# LVDS_IFC.net
KiCad netlist of a schematic drawn in Altium Designer
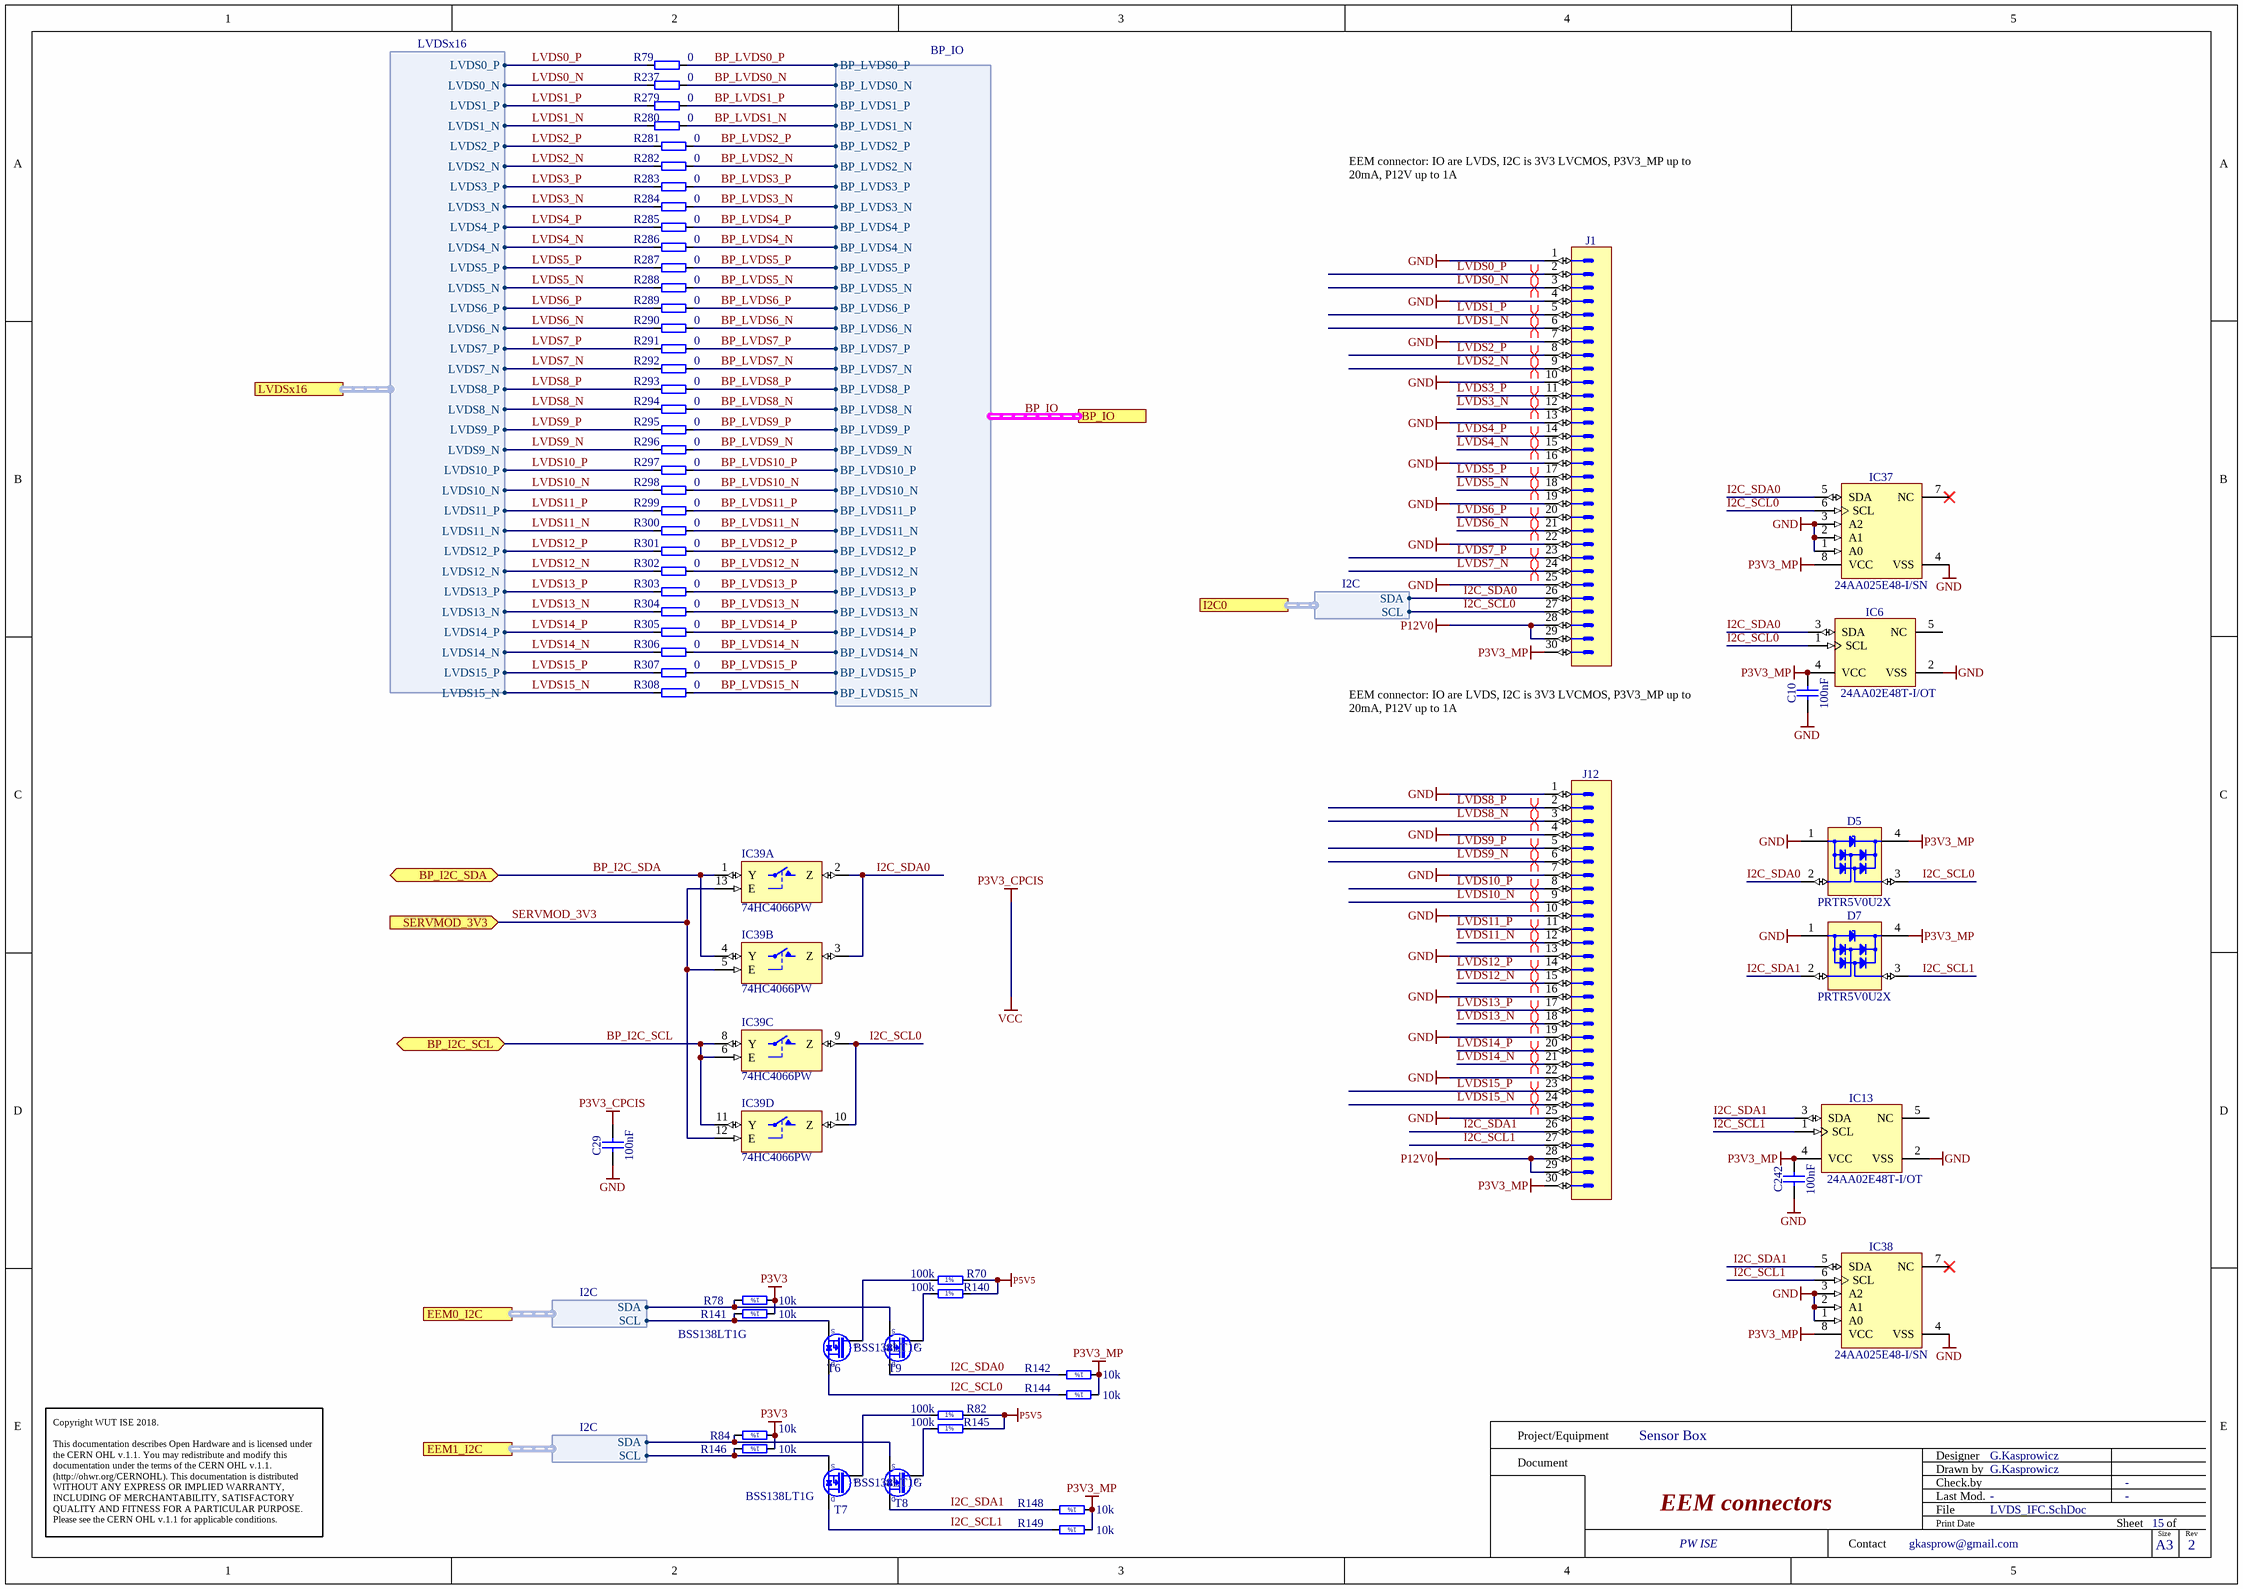
[diagram p0: LVDS_IFC.SchDoc]

(export (version "E")
  (design (tool "Eeschema 10.0.6"))
  (components
    (comp (ref "C10")
      (value "100nF")
      (footprint "CAPC1005X55N")
      (description "Non-polarised capacitor")
      (fields
        (field (name "PART NUMBER") "CC0402_100NF_16V_10%_X5R")
        (field (name "VOLTAGE") "16V")
        (field (name "AUTHOR") "CERN DEM JLC")
      )
      (libsource (lib "Capacitors") (part "Capacitor - non polarized"))
    )
    (comp (ref "C29")
      (value "100nF")
      (footprint "CAPC1005X55N")
      (description "Non-polarised capacitor")
      (fields
        (field (name "PART NUMBER") "CC0402_100NF_16V_10%_X5R")
        (field (name "VOLTAGE") "16V")
        (field (name "AUTHOR") "CERN DEM JLC")
      )
      (libsource (lib "Capacitors") (part "Capacitor - non polarized"))
    )
    (comp (ref "C242")
      (value "100nF")
      (footprint "CAPC1005X55N")
      (description "Non-polarised capacitor")
      (fields
        (field (name "PART NUMBER") "CC0402_100NF_16V_10%_X5R")
        (field (name "VOLTAGE") "16V")
        (field (name "AUTHOR") "CERN DEM JLC")
      )
      (libsource (lib "Capacitors") (part "Capacitor - non polarized"))
    )
    (comp (ref "D5")
      (value "PRTR5V0U2X")
      (footprint "SOT190P230X110-4N")
      (description "Ultra Low Capacitance Double Rail-to-Rail ESD Protection Diode")
      (fields
        (field (name "VOLTAGE") "5.5V")
        (field (name "MANUFACTURER") "NXP SEMICONDUCTORS")
        (field (name "AUTHOR") "CERN DEM JLC")
      )
      (libsource (lib "ICs And Semiconductors") (part "PRTR5V0U2X"))
    )
    (comp (ref "D7")
      (value "PRTR5V0U2X")
      (footprint "SOT190P230X110-4N")
      (description "Ultra Low Capacitance Double Rail-to-Rail ESD Protection Diode")
      (fields
        (field (name "VOLTAGE") "5.5V")
        (field (name "MANUFACTURER") "NXP SEMICONDUCTORS")
        (field (name "AUTHOR") "CERN DEM JLC")
      )
      (libsource (lib "ICs And Semiconductors") (part "PRTR5V0U2X"))
    )
    (comp (ref "IC6")
      (value "24AA02E48T-I/OT")
      (footprint "SOT95P280X145-5N")
      (description "1.7V-5.5V, 2K I2C Serial EEPROM With EUI-48 Node Identity")
      (fields (field (name "MANUFACTURER") "MICROCHIP TECHNOLOGY") (field (name "AUTHOR") "CERN DEM MR"))
      (libsource (lib "ICs And Semiconductors") (part "24AA02E48T-I/OT"))
    )
    (comp (ref "IC13")
      (value "24AA02E48T-I/OT")
      (footprint "SOT95P280X145-5N")
      (description "1.7V-5.5V, 2K I2C Serial EEPROM With EUI-48 Node Identity")
      (fields (field (name "MANUFACTURER") "MICROCHIP TECHNOLOGY") (field (name "AUTHOR") "CERN DEM MR"))
      (libsource (lib "ICs And Semiconductors") (part "24AA02E48T-I/OT"))
    )
    (comp (ref "IC37")
      (value "24AA025E48-I/SN")
      (footprint "SOIC127P600X175-8N")
      (description "1.7V-5.5V, 2K I2C™ Serial EEPROMs with EUI-48™ Node Identity")
      (fields (field (name "MANUFACTURER") "MICROCHIP TECHNOLOGY") (field (name "AUTHOR") "CERN DEM MR"))
      (libsource (lib "ICs And Semiconductors") (part "24AA025E48-I/SN"))
    )
    (comp (ref "IC38")
      (value "24AA025E48-I/SN")
      (footprint "SOIC127P600X175-8N")
      (description "1.7V-5.5V, 2K I2C™ Serial EEPROMs with EUI-48™ Node Identity")
      (fields (field (name "MANUFACTURER") "MICROCHIP TECHNOLOGY") (field (name "AUTHOR") "CERN DEM MR"))
      (libsource (lib "ICs And Semiconductors") (part "24AA025E48-I/SN"))
    )
    (comp (ref "IC39")
      (value "74HC4066PW")
      (footprint "SOP65P640X110-14N")
      (fields (field (name "MANUFACTURER") "NXP SEMICONDUCTORS") (field (name "AUTHOR") "CERN DEM JLC"))
      (libsource (lib "ICs And Semiconductors") (part "4066"))
    )
    (comp (ref "J1")
      (value "~")
      (footprint "3M_N2530-6002RB")
      (description "Connector 30 Male")
      (fields
        (field (name "PART NUMBER") "3M_N2530-6002RB")
        (field (name "MANUFACTURER") "3M")
        (field (name "AUTHOR") "CERN DEM JLC")
      )
      (libsource (lib "Connectors") (part "Connector 30 Male"))
    )
    (comp (ref "J12")
      (value "~")
      (footprint "3M_N2530-6002RB")
      (description "Connector 30 Male")
      (fields
        (field (name "PART NUMBER") "3M_N2530-6002RB")
        (field (name "MANUFACTURER") "3M")
        (field (name "AUTHOR") "CERN DEM JLC")
      )
      (libsource (lib "Connectors") (part "Connector 30 Male"))
    )
    (comp (ref "R70")
      (value "100k")
      (footprint "RESC1005X40N")
      (description "Resistor - 1%")
      (fields
        (field (name "PART NUMBER") "R0402_100K_1%_0.0625W_100PPM")
        (field (name "POWER") "0.0625W")
        (field (name "AUTHOR") "CERN DEM JLC")
      )
      (libsource (lib "Resistors") (part "Resistor - 1%"))
    )
    (comp (ref "R78")
      (value "10k")
      (footprint "RESC1005X40N")
      (description "Resistor - 1%")
      (fields
        (field (name "PART NUMBER") "R0402_10K_1%_0.0625W_100PPM")
        (field (name "POWER") "0.0625W")
        (field (name "AUTHOR") "CERN DEM JLC")
      )
      (libsource (lib "Resistors") (part "Resistor - 1%"))
    )
    (comp (ref "R79")
      (value "0")
      (footprint "RESC1005X35N")
      (description "Resistor")
      (fields
        (field (name "PART NUMBER") "R0402_0R_JUMPER")
        (field (name "MANUFACTURER") "GENERIC")
        (field (name "AUTHOR") "CERN DEM JLC")
      )
      (libsource (lib "Resistors") (part "Resistor"))
    )
    (comp (ref "R82")
      (value "100k")
      (footprint "RESC1005X40N")
      (description "Resistor - 1%")
      (fields
        (field (name "PART NUMBER") "R0402_100K_1%_0.0625W_100PPM")
        (field (name "POWER") "0.0625W")
        (field (name "AUTHOR") "CERN DEM JLC")
      )
      (libsource (lib "Resistors") (part "Resistor - 1%"))
    )
    (comp (ref "R84")
      (value "10k")
      (footprint "RESC1005X40N")
      (description "Resistor - 1%")
      (fields
        (field (name "PART NUMBER") "R0402_10K_1%_0.0625W_100PPM")
        (field (name "POWER") "0.0625W")
        (field (name "AUTHOR") "CERN DEM JLC")
      )
      (libsource (lib "Resistors") (part "Resistor - 1%"))
    )
    (comp (ref "R140")
      (value "100k")
      (footprint "RESC1005X40N")
      (description "Resistor - 1%")
      (fields
        (field (name "PART NUMBER") "R0402_100K_1%_0.0625W_100PPM")
        (field (name "POWER") "0.0625W")
        (field (name "AUTHOR") "CERN DEM JLC")
      )
      (libsource (lib "Resistors") (part "Resistor - 1%"))
    )
    (comp (ref "R141")
      (value "10k")
      (footprint "RESC1005X40N")
      (description "Resistor - 1%")
      (fields
        (field (name "PART NUMBER") "R0402_10K_1%_0.0625W_100PPM")
        (field (name "POWER") "0.0625W")
        (field (name "AUTHOR") "CERN DEM JLC")
      )
      (libsource (lib "Resistors") (part "Resistor - 1%"))
    )
    (comp (ref "R142")
      (value "10k")
      (footprint "RESC1005X40N")
      (description "Resistor - 1%")
      (fields
        (field (name "PART NUMBER") "R0402_10K_1%_0.0625W_100PPM")
        (field (name "POWER") "0.0625W")
        (field (name "AUTHOR") "CERN DEM JLC")
      )
      (libsource (lib "Resistors") (part "Resistor - 1%"))
    )
    (comp (ref "R144")
      (value "10k")
      (footprint "RESC1005X40N")
      (description "Resistor - 1%")
      (fields
        (field (name "PART NUMBER") "R0402_10K_1%_0.0625W_100PPM")
        (field (name "POWER") "0.0625W")
        (field (name "AUTHOR") "CERN DEM JLC")
      )
      (libsource (lib "Resistors") (part "Resistor - 1%"))
    )
    (comp (ref "R145")
      (value "100k")
      (footprint "RESC1005X40N")
      (description "Resistor - 1%")
      (fields
        (field (name "PART NUMBER") "R0402_100K_1%_0.0625W_100PPM")
        (field (name "POWER") "0.0625W")
        (field (name "AUTHOR") "CERN DEM JLC")
      )
      (libsource (lib "Resistors") (part "Resistor - 1%"))
    )
    (comp (ref "R146")
      (value "10k")
      (footprint "RESC1005X40N")
      (description "Resistor - 1%")
      (fields
        (field (name "PART NUMBER") "R0402_10K_1%_0.0625W_100PPM")
        (field (name "POWER") "0.0625W")
        (field (name "AUTHOR") "CERN DEM JLC")
      )
      (libsource (lib "Resistors") (part "Resistor - 1%"))
    )
    (comp (ref "R148")
      (value "10k")
      (footprint "RESC1005X40N")
      (description "Resistor - 1%")
      (fields
        (field (name "PART NUMBER") "R0402_10K_1%_0.0625W_100PPM")
        (field (name "POWER") "0.0625W")
        (field (name "AUTHOR") "CERN DEM JLC")
      )
      (libsource (lib "Resistors") (part "Resistor - 1%"))
    )
    (comp (ref "R149")
      (value "10k")
      (footprint "RESC1005X40N")
      (description "Resistor - 1%")
      (fields
        (field (name "PART NUMBER") "R0402_10K_1%_0.0625W_100PPM")
        (field (name "POWER") "0.0625W")
        (field (name "AUTHOR") "CERN DEM JLC")
      )
      (libsource (lib "Resistors") (part "Resistor - 1%"))
    )
    (comp (ref "R237")
      (value "0")
      (footprint "RESC1005X35N")
      (description "Resistor")
      (fields
        (field (name "PART NUMBER") "R0402_0R_JUMPER")
        (field (name "MANUFACTURER") "GENERIC")
        (field (name "AUTHOR") "CERN DEM JLC")
      )
      (libsource (lib "Resistors") (part "Resistor"))
    )
    (comp (ref "R279")
      (value "0")
      (footprint "RESC1005X35N")
      (description "Resistor")
      (fields
        (field (name "PART NUMBER") "R0402_0R_JUMPER")
        (field (name "MANUFACTURER") "GENERIC")
        (field (name "AUTHOR") "CERN DEM JLC")
      )
      (libsource (lib "Resistors") (part "Resistor"))
    )
    (comp (ref "R280")
      (value "0")
      (footprint "RESC1005X35N")
      (description "Resistor")
      (fields
        (field (name "PART NUMBER") "R0402_0R_JUMPER")
        (field (name "MANUFACTURER") "GENERIC")
        (field (name "AUTHOR") "CERN DEM JLC")
      )
      (libsource (lib "Resistors") (part "Resistor"))
    )
    (comp (ref "R281")
      (value "0")
      (footprint "RESC1005X35N")
      (description "Resistor")
      (fields
        (field (name "PART NUMBER") "R0402_0R_JUMPER")
        (field (name "MANUFACTURER") "GENERIC")
        (field (name "AUTHOR") "CERN DEM JLC")
      )
      (libsource (lib "Resistors") (part "Resistor"))
    )
    (comp (ref "R282")
      (value "0")
      (footprint "RESC1005X35N")
      (description "Resistor")
      (fields
        (field (name "PART NUMBER") "R0402_0R_JUMPER")
        (field (name "MANUFACTURER") "GENERIC")
        (field (name "AUTHOR") "CERN DEM JLC")
      )
      (libsource (lib "Resistors") (part "Resistor"))
    )
    (comp (ref "R283")
      (value "0")
      (footprint "RESC1005X35N")
      (description "Resistor")
      (fields
        (field (name "PART NUMBER") "R0402_0R_JUMPER")
        (field (name "MANUFACTURER") "GENERIC")
        (field (name "AUTHOR") "CERN DEM JLC")
      )
      (libsource (lib "Resistors") (part "Resistor"))
    )
    (comp (ref "R284")
      (value "0")
      (footprint "RESC1005X35N")
      (description "Resistor")
      (fields
        (field (name "PART NUMBER") "R0402_0R_JUMPER")
        (field (name "MANUFACTURER") "GENERIC")
        (field (name "AUTHOR") "CERN DEM JLC")
      )
      (libsource (lib "Resistors") (part "Resistor"))
    )
    (comp (ref "R285")
      (value "0")
      (footprint "RESC1005X35N")
      (description "Resistor")
      (fields
        (field (name "PART NUMBER") "R0402_0R_JUMPER")
        (field (name "MANUFACTURER") "GENERIC")
        (field (name "AUTHOR") "CERN DEM JLC")
      )
      (libsource (lib "Resistors") (part "Resistor"))
    )
    (comp (ref "R286")
      (value "0")
      (footprint "RESC1005X35N")
      (description "Resistor")
      (fields
        (field (name "PART NUMBER") "R0402_0R_JUMPER")
        (field (name "MANUFACTURER") "GENERIC")
        (field (name "AUTHOR") "CERN DEM JLC")
      )
      (libsource (lib "Resistors") (part "Resistor"))
    )
    (comp (ref "R287")
      (value "0")
      (footprint "RESC1005X35N")
      (description "Resistor")
      (fields
        (field (name "PART NUMBER") "R0402_0R_JUMPER")
        (field (name "MANUFACTURER") "GENERIC")
        (field (name "AUTHOR") "CERN DEM JLC")
      )
      (libsource (lib "Resistors") (part "Resistor"))
    )
    (comp (ref "R288")
      (value "0")
      (footprint "RESC1005X35N")
      (description "Resistor")
      (fields
        (field (name "PART NUMBER") "R0402_0R_JUMPER")
        (field (name "MANUFACTURER") "GENERIC")
        (field (name "AUTHOR") "CERN DEM JLC")
      )
      (libsource (lib "Resistors") (part "Resistor"))
    )
    (comp (ref "R289")
      (value "0")
      (footprint "RESC1005X35N")
      (description "Resistor")
      (fields
        (field (name "PART NUMBER") "R0402_0R_JUMPER")
        (field (name "MANUFACTURER") "GENERIC")
        (field (name "AUTHOR") "CERN DEM JLC")
      )
      (libsource (lib "Resistors") (part "Resistor"))
    )
    (comp (ref "R290")
      (value "0")
      (footprint "RESC1005X35N")
      (description "Resistor")
      (fields
        (field (name "PART NUMBER") "R0402_0R_JUMPER")
        (field (name "MANUFACTURER") "GENERIC")
        (field (name "AUTHOR") "CERN DEM JLC")
      )
      (libsource (lib "Resistors") (part "Resistor"))
    )
    (comp (ref "R291")
      (value "0")
      (footprint "RESC1005X35N")
      (description "Resistor")
      (fields
        (field (name "PART NUMBER") "R0402_0R_JUMPER")
        (field (name "MANUFACTURER") "GENERIC")
        (field (name "AUTHOR") "CERN DEM JLC")
      )
      (libsource (lib "Resistors") (part "Resistor"))
    )
    (comp (ref "R292")
      (value "0")
      (footprint "RESC1005X35N")
      (description "Resistor")
      (fields
        (field (name "PART NUMBER") "R0402_0R_JUMPER")
        (field (name "MANUFACTURER") "GENERIC")
        (field (name "AUTHOR") "CERN DEM JLC")
      )
      (libsource (lib "Resistors") (part "Resistor"))
    )
    (comp (ref "R293")
      (value "0")
      (footprint "RESC1005X35N")
      (description "Resistor")
      (fields
        (field (name "PART NUMBER") "R0402_0R_JUMPER")
        (field (name "MANUFACTURER") "GENERIC")
        (field (name "AUTHOR") "CERN DEM JLC")
      )
      (libsource (lib "Resistors") (part "Resistor"))
    )
    (comp (ref "R294")
      (value "0")
      (footprint "RESC1005X35N")
      (description "Resistor")
      (fields
        (field (name "PART NUMBER") "R0402_0R_JUMPER")
        (field (name "MANUFACTURER") "GENERIC")
        (field (name "AUTHOR") "CERN DEM JLC")
      )
      (libsource (lib "Resistors") (part "Resistor"))
    )
    (comp (ref "R295")
      (value "0")
      (footprint "RESC1005X35N")
      (description "Resistor")
      (fields
        (field (name "PART NUMBER") "R0402_0R_JUMPER")
        (field (name "MANUFACTURER") "GENERIC")
        (field (name "AUTHOR") "CERN DEM JLC")
      )
      (libsource (lib "Resistors") (part "Resistor"))
    )
    (comp (ref "R296")
      (value "0")
      (footprint "RESC1005X35N")
      (description "Resistor")
      (fields
        (field (name "PART NUMBER") "R0402_0R_JUMPER")
        (field (name "MANUFACTURER") "GENERIC")
        (field (name "AUTHOR") "CERN DEM JLC")
      )
      (libsource (lib "Resistors") (part "Resistor"))
    )
    (comp (ref "R297")
      (value "0")
      (footprint "RESC1005X35N")
      (description "Resistor")
      (fields
        (field (name "PART NUMBER") "R0402_0R_JUMPER")
        (field (name "MANUFACTURER") "GENERIC")
        (field (name "AUTHOR") "CERN DEM JLC")
      )
      (libsource (lib "Resistors") (part "Resistor"))
    )
    (comp (ref "R298")
      (value "0")
      (footprint "RESC1005X35N")
      (description "Resistor")
      (fields
        (field (name "PART NUMBER") "R0402_0R_JUMPER")
        (field (name "MANUFACTURER") "GENERIC")
        (field (name "AUTHOR") "CERN DEM JLC")
      )
      (libsource (lib "Resistors") (part "Resistor"))
    )
    (comp (ref "R299")
      (value "0")
      (footprint "RESC1005X35N")
      (description "Resistor")
      (fields
        (field (name "PART NUMBER") "R0402_0R_JUMPER")
        (field (name "MANUFACTURER") "GENERIC")
        (field (name "AUTHOR") "CERN DEM JLC")
      )
      (libsource (lib "Resistors") (part "Resistor"))
    )
    (comp (ref "R300")
      (value "0")
      (footprint "RESC1005X35N")
      (description "Resistor")
      (fields
        (field (name "PART NUMBER") "R0402_0R_JUMPER")
        (field (name "MANUFACTURER") "GENERIC")
        (field (name "AUTHOR") "CERN DEM JLC")
      )
      (libsource (lib "Resistors") (part "Resistor"))
    )
    (comp (ref "R301")
      (value "0")
      (footprint "RESC1005X35N")
      (description "Resistor")
      (fields
        (field (name "PART NUMBER") "R0402_0R_JUMPER")
        (field (name "MANUFACTURER") "GENERIC")
        (field (name "AUTHOR") "CERN DEM JLC")
      )
      (libsource (lib "Resistors") (part "Resistor"))
    )
    (comp (ref "R302")
      (value "0")
      (footprint "RESC1005X35N")
      (description "Resistor")
      (fields
        (field (name "PART NUMBER") "R0402_0R_JUMPER")
        (field (name "MANUFACTURER") "GENERIC")
        (field (name "AUTHOR") "CERN DEM JLC")
      )
      (libsource (lib "Resistors") (part "Resistor"))
    )
    (comp (ref "R303")
      (value "0")
      (footprint "RESC1005X35N")
      (description "Resistor")
      (fields
        (field (name "PART NUMBER") "R0402_0R_JUMPER")
        (field (name "MANUFACTURER") "GENERIC")
        (field (name "AUTHOR") "CERN DEM JLC")
      )
      (libsource (lib "Resistors") (part "Resistor"))
    )
    (comp (ref "R304")
      (value "0")
      (footprint "RESC1005X35N")
      (description "Resistor")
      (fields
        (field (name "PART NUMBER") "R0402_0R_JUMPER")
        (field (name "MANUFACTURER") "GENERIC")
        (field (name "AUTHOR") "CERN DEM JLC")
      )
      (libsource (lib "Resistors") (part "Resistor"))
    )
    (comp (ref "R305")
      (value "0")
      (footprint "RESC1005X35N")
      (description "Resistor")
      (fields
        (field (name "PART NUMBER") "R0402_0R_JUMPER")
        (field (name "MANUFACTURER") "GENERIC")
        (field (name "AUTHOR") "CERN DEM JLC")
      )
      (libsource (lib "Resistors") (part "Resistor"))
    )
    (comp (ref "R306")
      (value "0")
      (footprint "RESC1005X35N")
      (description "Resistor")
      (fields
        (field (name "PART NUMBER") "R0402_0R_JUMPER")
        (field (name "MANUFACTURER") "GENERIC")
        (field (name "AUTHOR") "CERN DEM JLC")
      )
      (libsource (lib "Resistors") (part "Resistor"))
    )
    (comp (ref "R307")
      (value "0")
      (footprint "RESC1005X35N")
      (description "Resistor")
      (fields
        (field (name "PART NUMBER") "R0402_0R_JUMPER")
        (field (name "MANUFACTURER") "GENERIC")
        (field (name "AUTHOR") "CERN DEM JLC")
      )
      (libsource (lib "Resistors") (part "Resistor"))
    )
    (comp (ref "R308")
      (value "0")
      (footprint "RESC1005X35N")
      (description "Resistor")
      (fields
        (field (name "PART NUMBER") "R0402_0R_JUMPER")
        (field (name "MANUFACTURER") "GENERIC")
        (field (name "AUTHOR") "CERN DEM JLC")
      )
      (libsource (lib "Resistors") (part "Resistor"))
    )
    (comp (ref "T6")
      (value "BSS138LT1G")
      (footprint "SOT95P240X110-3N")
      (description "N-CHANNEL MOSFET WITH DIODE")
      (fields (field (name "MANUFACTURER") "ON SEMICONDUCTOR") (field (name "AUTHOR") "CERN DEM JLC"))
      (libsource (lib "ICs And Semiconductors") (part "N-MOSFET-D 1G 2S 3D"))
    )
    (comp (ref "T7")
      (value "BSS138LT1G")
      (footprint "SOT95P240X110-3N")
      (description "N-CHANNEL MOSFET WITH DIODE")
      (fields (field (name "MANUFACTURER") "ON SEMICONDUCTOR") (field (name "AUTHOR") "CERN DEM JLC"))
      (libsource (lib "ICs And Semiconductors") (part "N-MOSFET-D 1G 2S 3D"))
    )
    (comp (ref "T8")
      (value "BSS138LT1G")
      (footprint "SOT95P240X110-3N")
      (description "N-CHANNEL MOSFET WITH DIODE")
      (fields (field (name "MANUFACTURER") "ON SEMICONDUCTOR") (field (name "AUTHOR") "CERN DEM JLC"))
      (libsource (lib "ICs And Semiconductors") (part "N-MOSFET-D 1G 2S 3D"))
    )
    (comp (ref "T9")
      (value "BSS138LT1G")
      (footprint "SOT95P240X110-3N")
      (description "N-CHANNEL MOSFET WITH DIODE")
      (fields (field (name "MANUFACTURER") "ON SEMICONDUCTOR") (field (name "AUTHOR") "CERN DEM JLC"))
      (libsource (lib "ICs And Semiconductors") (part "N-MOSFET-D 1G 2S 3D"))
    )
  )
  (nets
    (net (code "4") (name "/BP_I2C_SCL") (class "Default")
      (node (ref "IC39") (pin "11") (pinfunction "Y_11") (pintype "bidirectional"))
      (node (ref "IC39") (pin "6") (pinfunction "E_6") (pintype "input"))
      (node (ref "IC39") (pin "8") (pinfunction "Y_8") (pintype "bidirectional"))
    )
    (net (code "5") (name "/BP_I2C_SDA") (class "Default")
      (node (ref "IC39") (pin "1") (pinfunction "Y_1") (pintype "bidirectional"))
      (node (ref "IC39") (pin "4") (pinfunction "Y_4") (pintype "bidirectional"))
    )
    (net (code "7") (name "/BP_LVDS0_N") (class "Default")
      (node (ref "R237") (pin "1") (pinfunction "1_1") (pintype "passive"))
    )
    (net (code "8") (name "/BP_LVDS0_P") (class "Default")
      (node (ref "R79") (pin "1") (pinfunction "1_1") (pintype "passive"))
    )
    (net (code "9") (name "/BP_LVDS1_N") (class "Default")
      (node (ref "R280") (pin "1") (pinfunction "1_1") (pintype "passive"))
    )
    (net (code "10") (name "/BP_LVDS1_P") (class "Default")
      (node (ref "R279") (pin "1") (pinfunction "1_1") (pintype "passive"))
    )
    (net (code "11") (name "/BP_LVDS2_N") (class "Default")
      (node (ref "R282") (pin "1") (pinfunction "1_1") (pintype "passive"))
    )
    (net (code "12") (name "/BP_LVDS2_P") (class "Default")
      (node (ref "R281") (pin "1") (pinfunction "1_1") (pintype "passive"))
    )
    (net (code "13") (name "/BP_LVDS3_N") (class "Default")
      (node (ref "R284") (pin "1") (pinfunction "1_1") (pintype "passive"))
    )
    (net (code "14") (name "/BP_LVDS3_P") (class "Default")
      (node (ref "R283") (pin "1") (pinfunction "1_1") (pintype "passive"))
    )
    (net (code "15") (name "/BP_LVDS4_N") (class "Default")
      (node (ref "R286") (pin "1") (pinfunction "1_1") (pintype "passive"))
    )
    (net (code "16") (name "/BP_LVDS4_P") (class "Default")
      (node (ref "R285") (pin "1") (pinfunction "1_1") (pintype "passive"))
    )
    (net (code "17") (name "/BP_LVDS5_N") (class "Default")
      (node (ref "R288") (pin "1") (pinfunction "1_1") (pintype "passive"))
    )
    (net (code "18") (name "/BP_LVDS5_P") (class "Default")
      (node (ref "R287") (pin "1") (pinfunction "1_1") (pintype "passive"))
    )
    (net (code "19") (name "/BP_LVDS6_N") (class "Default")
      (node (ref "R290") (pin "1") (pinfunction "1_1") (pintype "passive"))
    )
    (net (code "20") (name "/BP_LVDS6_P") (class "Default")
      (node (ref "R289") (pin "1") (pinfunction "1_1") (pintype "passive"))
    )
    (net (code "21") (name "/BP_LVDS7_N") (class "Default")
      (node (ref "R292") (pin "1") (pinfunction "1_1") (pintype "passive"))
    )
    (net (code "22") (name "/BP_LVDS7_P") (class "Default")
      (node (ref "R291") (pin "1") (pinfunction "1_1") (pintype "passive"))
    )
    (net (code "23") (name "/BP_LVDS8_N") (class "Default")
      (node (ref "R294") (pin "1") (pinfunction "1_1") (pintype "passive"))
    )
    (net (code "24") (name "/BP_LVDS8_P") (class "Default")
      (node (ref "R293") (pin "1") (pinfunction "1_1") (pintype "passive"))
    )
    (net (code "25") (name "/BP_LVDS9_N") (class "Default")
      (node (ref "R296") (pin "1") (pinfunction "1_1") (pintype "passive"))
    )
    (net (code "26") (name "/BP_LVDS9_P") (class "Default")
      (node (ref "R295") (pin "1") (pinfunction "1_1") (pintype "passive"))
    )
    (net (code "27") (name "/BP_LVDS10_N") (class "Default")
      (node (ref "R298") (pin "1") (pinfunction "1_1") (pintype "passive"))
    )
    (net (code "28") (name "/BP_LVDS10_P") (class "Default")
      (node (ref "R297") (pin "1") (pinfunction "1_1") (pintype "passive"))
    )
    (net (code "29") (name "/BP_LVDS11_N") (class "Default")
      (node (ref "R300") (pin "1") (pinfunction "1_1") (pintype "passive"))
    )
    (net (code "30") (name "/BP_LVDS11_P") (class "Default")
      (node (ref "R299") (pin "1") (pinfunction "1_1") (pintype "passive"))
    )
    (net (code "31") (name "/BP_LVDS12_N") (class "Default")
      (node (ref "R302") (pin "1") (pinfunction "1_1") (pintype "passive"))
    )
    (net (code "32") (name "/BP_LVDS12_P") (class "Default")
      (node (ref "R301") (pin "1") (pinfunction "1_1") (pintype "passive"))
    )
    (net (code "33") (name "/BP_LVDS13_N") (class "Default")
      (node (ref "R304") (pin "1") (pinfunction "1_1") (pintype "passive"))
    )
    (net (code "34") (name "/BP_LVDS13_P") (class "Default")
      (node (ref "R303") (pin "1") (pinfunction "1_1") (pintype "passive"))
    )
    (net (code "35") (name "/BP_LVDS14_N") (class "Default")
      (node (ref "R306") (pin "1") (pinfunction "1_1") (pintype "passive"))
    )
    (net (code "36") (name "/BP_LVDS14_P") (class "Default")
      (node (ref "R305") (pin "1") (pinfunction "1_1") (pintype "passive"))
    )
    (net (code "37") (name "/BP_LVDS15_N") (class "Default")
      (node (ref "R308") (pin "1") (pinfunction "1_1") (pintype "passive"))
    )
    (net (code "38") (name "/BP_LVDS15_P") (class "Default")
      (node (ref "R307") (pin "1") (pinfunction "1_1") (pintype "passive"))
    )
    (net (code "39") (name "/I2C_SCL0") (class "Default")
      (node (ref "D5") (pin "3") (pinfunction "I/O2_3") (pintype "bidirectional"))
      (node (ref "IC37") (pin "6") (pinfunction "SCL_6") (pintype "input"))
      (node (ref "IC39") (pin "10") (pinfunction "Z_10") (pintype "bidirectional"))
      (node (ref "IC39") (pin "9") (pinfunction "Z_9") (pintype "bidirectional"))
      (node (ref "IC6") (pin "1") (pinfunction "SCL_1") (pintype "input"))
      (node (ref "J1") (pin "27") (pinfunction "27_27") (pintype "bidirectional"))
      (node (ref "R144") (pin "2") (pinfunction "2_2") (pintype "passive"))
      (node (ref "T6") (pin "3") (pinfunction "D_3") (pintype "passive"))
    )
    (net (code "40") (name "/I2C_SCL1") (class "Default")
      (node (ref "D7") (pin "3") (pinfunction "I/O2_3") (pintype "bidirectional"))
      (node (ref "IC13") (pin "1") (pinfunction "SCL_1") (pintype "input"))
      (node (ref "IC38") (pin "6") (pinfunction "SCL_6") (pintype "input"))
      (node (ref "J12") (pin "27") (pinfunction "27_27") (pintype "bidirectional"))
      (node (ref "R149") (pin "2") (pinfunction "2_2") (pintype "passive"))
      (node (ref "T7") (pin "3") (pinfunction "D_3") (pintype "passive"))
    )
    (net (code "41") (name "/I2C_SDA0") (class "Default")
      (node (ref "D5") (pin "2") (pinfunction "I/O1_2") (pintype "bidirectional"))
      (node (ref "IC37") (pin "5") (pinfunction "SDA_5") (pintype "bidirectional"))
      (node (ref "IC39") (pin "2") (pinfunction "Z_2") (pintype "bidirectional"))
      (node (ref "IC39") (pin "3") (pinfunction "Z_3") (pintype "bidirectional"))
      (node (ref "IC6") (pin "3") (pinfunction "SDA_3") (pintype "bidirectional"))
      (node (ref "J1") (pin "26") (pinfunction "26_26") (pintype "bidirectional"))
      (node (ref "R142") (pin "2") (pinfunction "2_2") (pintype "passive"))
      (node (ref "T9") (pin "3") (pinfunction "D_3") (pintype "passive"))
    )
    (net (code "42") (name "/I2C_SDA1") (class "Default")
      (node (ref "D7") (pin "2") (pinfunction "I/O1_2") (pintype "bidirectional"))
      (node (ref "IC13") (pin "3") (pinfunction "SDA_3") (pintype "bidirectional"))
      (node (ref "IC38") (pin "5") (pinfunction "SDA_5") (pintype "bidirectional"))
      (node (ref "J12") (pin "26") (pinfunction "26_26") (pintype "bidirectional"))
      (node (ref "R148") (pin "2") (pinfunction "2_2") (pintype "passive"))
      (node (ref "T8") (pin "3") (pinfunction "D_3") (pintype "passive"))
    )
    (net (code "43") (name "/LVDS0_N") (class "Default")
      (node (ref "J1") (pin "3") (pinfunction "3_3") (pintype "bidirectional"))
      (node (ref "R237") (pin "2") (pinfunction "2_2") (pintype "passive"))
    )
    (net (code "44") (name "/LVDS0_P") (class "Default")
      (node (ref "J1") (pin "2") (pinfunction "2_2") (pintype "bidirectional"))
      (node (ref "R79") (pin "2") (pinfunction "2_2") (pintype "passive"))
    )
    (net (code "45") (name "/LVDS1_N") (class "Default")
      (node (ref "J1") (pin "6") (pinfunction "6_6") (pintype "bidirectional"))
      (node (ref "R280") (pin "2") (pinfunction "2_2") (pintype "passive"))
    )
    (net (code "46") (name "/LVDS1_P") (class "Default")
      (node (ref "J1") (pin "5") (pinfunction "5_5") (pintype "bidirectional"))
      (node (ref "R279") (pin "2") (pinfunction "2_2") (pintype "passive"))
    )
    (net (code "47") (name "/LVDS2_N") (class "Default")
      (node (ref "J1") (pin "9") (pinfunction "9_9") (pintype "bidirectional"))
      (node (ref "R282") (pin "2") (pinfunction "2_2") (pintype "passive"))
    )
    (net (code "48") (name "/LVDS2_P") (class "Default")
      (node (ref "J1") (pin "8") (pinfunction "8_8") (pintype "bidirectional"))
      (node (ref "R281") (pin "2") (pinfunction "2_2") (pintype "passive"))
    )
    (net (code "49") (name "/LVDS3_N") (class "Default")
      (node (ref "J1") (pin "12") (pinfunction "12_12") (pintype "bidirectional"))
      (node (ref "R284") (pin "2") (pinfunction "2_2") (pintype "passive"))
    )
    (net (code "50") (name "/LVDS3_P") (class "Default")
      (node (ref "J1") (pin "11") (pinfunction "11_11") (pintype "bidirectional"))
      (node (ref "R283") (pin "2") (pinfunction "2_2") (pintype "passive"))
    )
    (net (code "51") (name "/LVDS4_N") (class "Default")
      (node (ref "J1") (pin "15") (pinfunction "15_15") (pintype "bidirectional"))
      (node (ref "R286") (pin "2") (pinfunction "2_2") (pintype "passive"))
    )
    (net (code "52") (name "/LVDS4_P") (class "Default")
      (node (ref "J1") (pin "14") (pinfunction "14_14") (pintype "bidirectional"))
      (node (ref "R285") (pin "2") (pinfunction "2_2") (pintype "passive"))
    )
    (net (code "53") (name "/LVDS5_N") (class "Default")
      (node (ref "J1") (pin "18") (pinfunction "18_18") (pintype "bidirectional"))
      (node (ref "R288") (pin "2") (pinfunction "2_2") (pintype "passive"))
    )
    (net (code "54") (name "/LVDS5_P") (class "Default")
      (node (ref "J1") (pin "17") (pinfunction "17_17") (pintype "bidirectional"))
      (node (ref "R287") (pin "2") (pinfunction "2_2") (pintype "passive"))
    )
    (net (code "55") (name "/LVDS6_N") (class "Default")
      (node (ref "J1") (pin "21") (pinfunction "21_21") (pintype "bidirectional"))
      (node (ref "R290") (pin "2") (pinfunction "2_2") (pintype "passive"))
    )
    (net (code "56") (name "/LVDS6_P") (class "Default")
      (node (ref "J1") (pin "20") (pinfunction "20_20") (pintype "bidirectional"))
      (node (ref "R289") (pin "2") (pinfunction "2_2") (pintype "passive"))
    )
    (net (code "57") (name "/LVDS7_N") (class "Default")
      (node (ref "J1") (pin "24") (pinfunction "24_24") (pintype "bidirectional"))
      (node (ref "R292") (pin "2") (pinfunction "2_2") (pintype "passive"))
    )
    (net (code "58") (name "/LVDS7_P") (class "Default")
      (node (ref "J1") (pin "23") (pinfunction "23_23") (pintype "bidirectional"))
      (node (ref "R291") (pin "2") (pinfunction "2_2") (pintype "passive"))
    )
    (net (code "59") (name "/LVDS8_N") (class "Default")
      (node (ref "J12") (pin "3") (pinfunction "3_3") (pintype "bidirectional"))
      (node (ref "R294") (pin "2") (pinfunction "2_2") (pintype "passive"))
    )
    (net (code "60") (name "/LVDS8_P") (class "Default")
      (node (ref "J12") (pin "2") (pinfunction "2_2") (pintype "bidirectional"))
      (node (ref "R293") (pin "2") (pinfunction "2_2") (pintype "passive"))
    )
    (net (code "61") (name "/LVDS9_N") (class "Default")
      (node (ref "J12") (pin "6") (pinfunction "6_6") (pintype "bidirectional"))
      (node (ref "R296") (pin "2") (pinfunction "2_2") (pintype "passive"))
    )
    (net (code "62") (name "/LVDS9_P") (class "Default")
      (node (ref "J12") (pin "5") (pinfunction "5_5") (pintype "bidirectional"))
      (node (ref "R295") (pin "2") (pinfunction "2_2") (pintype "passive"))
    )
    (net (code "63") (name "/LVDS10_N") (class "Default")
      (node (ref "J12") (pin "9") (pinfunction "9_9") (pintype "bidirectional"))
      (node (ref "R298") (pin "2") (pinfunction "2_2") (pintype "passive"))
    )
    (net (code "64") (name "/LVDS10_P") (class "Default")
      (node (ref "J12") (pin "8") (pinfunction "8_8") (pintype "bidirectional"))
      (node (ref "R297") (pin "2") (pinfunction "2_2") (pintype "passive"))
    )
    (net (code "65") (name "/LVDS11_N") (class "Default")
      (node (ref "J12") (pin "12") (pinfunction "12_12") (pintype "bidirectional"))
      (node (ref "R300") (pin "2") (pinfunction "2_2") (pintype "passive"))
    )
    (net (code "66") (name "/LVDS11_P") (class "Default")
      (node (ref "J12") (pin "11") (pinfunction "11_11") (pintype "bidirectional"))
      (node (ref "R299") (pin "2") (pinfunction "2_2") (pintype "passive"))
    )
    (net (code "67") (name "/LVDS12_N") (class "Default")
      (node (ref "J12") (pin "15") (pinfunction "15_15") (pintype "bidirectional"))
      (node (ref "R302") (pin "2") (pinfunction "2_2") (pintype "passive"))
    )
    (net (code "68") (name "/LVDS12_P") (class "Default")
      (node (ref "J12") (pin "14") (pinfunction "14_14") (pintype "bidirectional"))
      (node (ref "R301") (pin "2") (pinfunction "2_2") (pintype "passive"))
    )
    (net (code "69") (name "/LVDS13_N") (class "Default")
      (node (ref "J12") (pin "18") (pinfunction "18_18") (pintype "bidirectional"))
      (node (ref "R304") (pin "2") (pinfunction "2_2") (pintype "passive"))
    )
    (net (code "70") (name "/LVDS13_P") (class "Default")
      (node (ref "J12") (pin "17") (pinfunction "17_17") (pintype "bidirectional"))
      (node (ref "R303") (pin "2") (pinfunction "2_2") (pintype "passive"))
    )
    (net (code "71") (name "/LVDS14_N") (class "Default")
      (node (ref "J12") (pin "21") (pinfunction "21_21") (pintype "bidirectional"))
      (node (ref "R306") (pin "2") (pinfunction "2_2") (pintype "passive"))
    )
    (net (code "72") (name "/LVDS14_P") (class "Default")
      (node (ref "J12") (pin "20") (pinfunction "20_20") (pintype "bidirectional"))
      (node (ref "R305") (pin "2") (pinfunction "2_2") (pintype "passive"))
    )
    (net (code "73") (name "/LVDS15_N") (class "Default")
      (node (ref "J12") (pin "24") (pinfunction "24_24") (pintype "bidirectional"))
      (node (ref "R308") (pin "2") (pinfunction "2_2") (pintype "passive"))
    )
    (net (code "74") (name "/LVDS15_P") (class "Default")
      (node (ref "J12") (pin "23") (pinfunction "23_23") (pintype "bidirectional"))
      (node (ref "R307") (pin "2") (pinfunction "2_2") (pintype "passive"))
    )
    (net (code "75") (name "/SERVMOD_3V3") (class "Default")
      (node (ref "IC39") (pin "12") (pinfunction "E_12") (pintype "input"))
      (node (ref "IC39") (pin "13") (pinfunction "E_13") (pintype "input"))
      (node (ref "IC39") (pin "5") (pinfunction "E_5") (pintype "input"))
    )
    (net (code "78") (name "GND") (class "Default")
      (node (ref "C10") (pin "1") (pinfunction "1_1") (pintype "passive"))
      (node (ref "C242") (pin "1") (pinfunction "1_1") (pintype "passive"))
      (node (ref "C29") (pin "1") (pinfunction "1_1") (pintype "passive"))
      (node (ref "D5") (pin "1") (pinfunction "GND_1") (pintype "power_in"))
      (node (ref "D7") (pin "1") (pinfunction "GND_1") (pintype "power_in"))
      (node (ref "IC13") (pin "2") (pinfunction "VSS_2") (pintype "power_in"))
      (node (ref "IC37") (pin "1") (pinfunction "A0_1") (pintype "input"))
      (node (ref "IC37") (pin "2") (pinfunction "A1_2") (pintype "input"))
      (node (ref "IC37") (pin "3") (pinfunction "A2_3") (pintype "input"))
      (node (ref "IC37") (pin "4") (pinfunction "VSS_4") (pintype "power_in"))
      (node (ref "IC38") (pin "1") (pinfunction "A0_1") (pintype "input"))
      (node (ref "IC38") (pin "2") (pinfunction "A1_2") (pintype "input"))
      (node (ref "IC38") (pin "3") (pinfunction "A2_3") (pintype "input"))
      (node (ref "IC38") (pin "4") (pinfunction "VSS_4") (pintype "power_in"))
      (node (ref "IC39") (pin "7") (pinfunction "GND_7") (pintype "power_in"))
      (node (ref "IC6") (pin "2") (pinfunction "VSS_2") (pintype "power_in"))
      (node (ref "J1") (pin "1") (pinfunction "1_1") (pintype "bidirectional"))
      (node (ref "J1") (pin "10") (pinfunction "10_10") (pintype "bidirectional"))
      (node (ref "J1") (pin "13") (pinfunction "13_13") (pintype "bidirectional"))
      (node (ref "J1") (pin "16") (pinfunction "16_16") (pintype "bidirectional"))
      (node (ref "J1") (pin "19") (pinfunction "19_19") (pintype "bidirectional"))
      (node (ref "J1") (pin "22") (pinfunction "22_22") (pintype "bidirectional"))
      (node (ref "J1") (pin "25") (pinfunction "25_25") (pintype "bidirectional"))
      (node (ref "J1") (pin "4") (pinfunction "4_4") (pintype "bidirectional"))
      (node (ref "J1") (pin "7") (pinfunction "7_7") (pintype "bidirectional"))
      (node (ref "J12") (pin "1") (pinfunction "1_1") (pintype "bidirectional"))
      (node (ref "J12") (pin "10") (pinfunction "10_10") (pintype "bidirectional"))
      (node (ref "J12") (pin "13") (pinfunction "13_13") (pintype "bidirectional"))
      (node (ref "J12") (pin "16") (pinfunction "16_16") (pintype "bidirectional"))
      (node (ref "J12") (pin "19") (pinfunction "19_19") (pintype "bidirectional"))
      (node (ref "J12") (pin "22") (pinfunction "22_22") (pintype "bidirectional"))
      (node (ref "J12") (pin "25") (pinfunction "25_25") (pintype "bidirectional"))
      (node (ref "J12") (pin "4") (pinfunction "4_4") (pintype "bidirectional"))
      (node (ref "J12") (pin "7") (pinfunction "7_7") (pintype "bidirectional"))
    )
    (net (code "79") (name "Net-(T6-G)") (class "Default")
      (node (ref "R70") (pin "1") (pinfunction "1_1") (pintype "passive"))
      (node (ref "T6") (pin "1") (pinfunction "G_1") (pintype "passive"))
    )
    (net (code "80") (name "Net-(T6-S)") (class "Default")
      (node (ref "R141") (pin "2") (pinfunction "2_2") (pintype "passive"))
      (node (ref "T6") (pin "2") (pinfunction "S_2") (pintype "passive"))
    )
    (net (code "81") (name "Net-(T7-G)") (class "Default")
      (node (ref "R82") (pin "1") (pinfunction "1_1") (pintype "passive"))
      (node (ref "T7") (pin "1") (pinfunction "G_1") (pintype "passive"))
    )
    (net (code "82") (name "Net-(T7-S)") (class "Default")
      (node (ref "R146") (pin "2") (pinfunction "2_2") (pintype "passive"))
      (node (ref "T7") (pin "2") (pinfunction "S_2") (pintype "passive"))
    )
    (net (code "83") (name "Net-(T8-G)") (class "Default")
      (node (ref "R145") (pin "1") (pinfunction "1_1") (pintype "passive"))
      (node (ref "T8") (pin "1") (pinfunction "G_1") (pintype "passive"))
    )
    (net (code "84") (name "Net-(T8-S)") (class "Default")
      (node (ref "R84") (pin "2") (pinfunction "2_2") (pintype "passive"))
      (node (ref "T8") (pin "2") (pinfunction "S_2") (pintype "passive"))
    )
    (net (code "85") (name "Net-(T9-G)") (class "Default")
      (node (ref "R140") (pin "1") (pinfunction "1_1") (pintype "passive"))
      (node (ref "T9") (pin "1") (pinfunction "G_1") (pintype "passive"))
    )
    (net (code "86") (name "Net-(T9-S)") (class "Default")
      (node (ref "R78") (pin "2") (pinfunction "2_2") (pintype "passive"))
      (node (ref "T9") (pin "2") (pinfunction "S_2") (pintype "passive"))
    )
    (net (code "87") (name "P3V3") (class "Default")
      (node (ref "R141") (pin "1") (pinfunction "1_1") (pintype "passive"))
      (node (ref "R146") (pin "1") (pinfunction "1_1") (pintype "passive"))
      (node (ref "R78") (pin "1") (pinfunction "1_1") (pintype "passive"))
      (node (ref "R84") (pin "1") (pinfunction "1_1") (pintype "passive"))
    )
    (net (code "88") (name "P3V3_CPCIS") (class "Default")
      (node (ref "C29") (pin "2") (pinfunction "2_2") (pintype "passive"))
      (node (ref "IC39") (pin "14") (pinfunction "VCC_14") (pintype "power_in"))
    )
    (net (code "89") (name "P3V3_MP") (class "Default")
      (node (ref "C10") (pin "2") (pinfunction "2_2") (pintype "passive"))
      (node (ref "C242") (pin "2") (pinfunction "2_2") (pintype "passive"))
      (node (ref "D5") (pin "4") (pinfunction "VCC_4") (pintype "power_in"))
      (node (ref "D7") (pin "4") (pinfunction "VCC_4") (pintype "power_in"))
      (node (ref "IC13") (pin "4") (pinfunction "VCC_4") (pintype "power_in"))
      (node (ref "IC37") (pin "8") (pinfunction "VCC_8") (pintype "power_in"))
      (node (ref "IC38") (pin "8") (pinfunction "VCC_8") (pintype "power_in"))
      (node (ref "IC6") (pin "4") (pinfunction "VCC_4") (pintype "power_in"))
      (node (ref "J1") (pin "30") (pinfunction "30_30") (pintype "bidirectional"))
      (node (ref "J12") (pin "30") (pinfunction "30_30") (pintype "bidirectional"))
      (node (ref "R142") (pin "1") (pinfunction "1_1") (pintype "passive"))
      (node (ref "R144") (pin "1") (pinfunction "1_1") (pintype "passive"))
      (node (ref "R148") (pin "1") (pinfunction "1_1") (pintype "passive"))
      (node (ref "R149") (pin "1") (pinfunction "1_1") (pintype "passive"))
    )
    (net (code "90") (name "P5V5") (class "Default")
      (node (ref "R140") (pin "2") (pinfunction "2_2") (pintype "passive"))
      (node (ref "R145") (pin "2") (pinfunction "2_2") (pintype "passive"))
      (node (ref "R70") (pin "2") (pinfunction "2_2") (pintype "passive"))
      (node (ref "R82") (pin "2") (pinfunction "2_2") (pintype "passive"))
    )
    (net (code "91") (name "P12V0") (class "Default")
      (node (ref "J1") (pin "28") (pinfunction "28_28") (pintype "bidirectional"))
      (node (ref "J1") (pin "29") (pinfunction "29_29") (pintype "bidirectional"))
      (node (ref "J12") (pin "28") (pinfunction "28_28") (pintype "bidirectional"))
      (node (ref "J12") (pin "29") (pinfunction "29_29") (pintype "bidirectional"))
    )
    (net (code "92") (name "unconnected-(IC6-NC-Pad5)") (class "Default")
      (node (ref "IC6") (pin "5") (pinfunction "NC_5") (pintype "passive"))
    )
    (net (code "93") (name "unconnected-(IC13-NC-Pad5)") (class "Default")
      (node (ref "IC13") (pin "5") (pinfunction "NC_5") (pintype "passive"))
    )
    (net (code "94") (name "unconnected-(IC37-NC-Pad7)") (class "Default")
      (node (ref "IC37") (pin "7") (pinfunction "NC_7") (pintype "passive+no_connect"))
    )
    (net (code "95") (name "unconnected-(IC38-NC-Pad7)") (class "Default")
      (node (ref "IC38") (pin "7") (pinfunction "NC_7") (pintype "passive+no_connect"))
    )
  )
)
